# Esp32_USB.net
KiCad netlist of a schematic drawn in Altium Designer
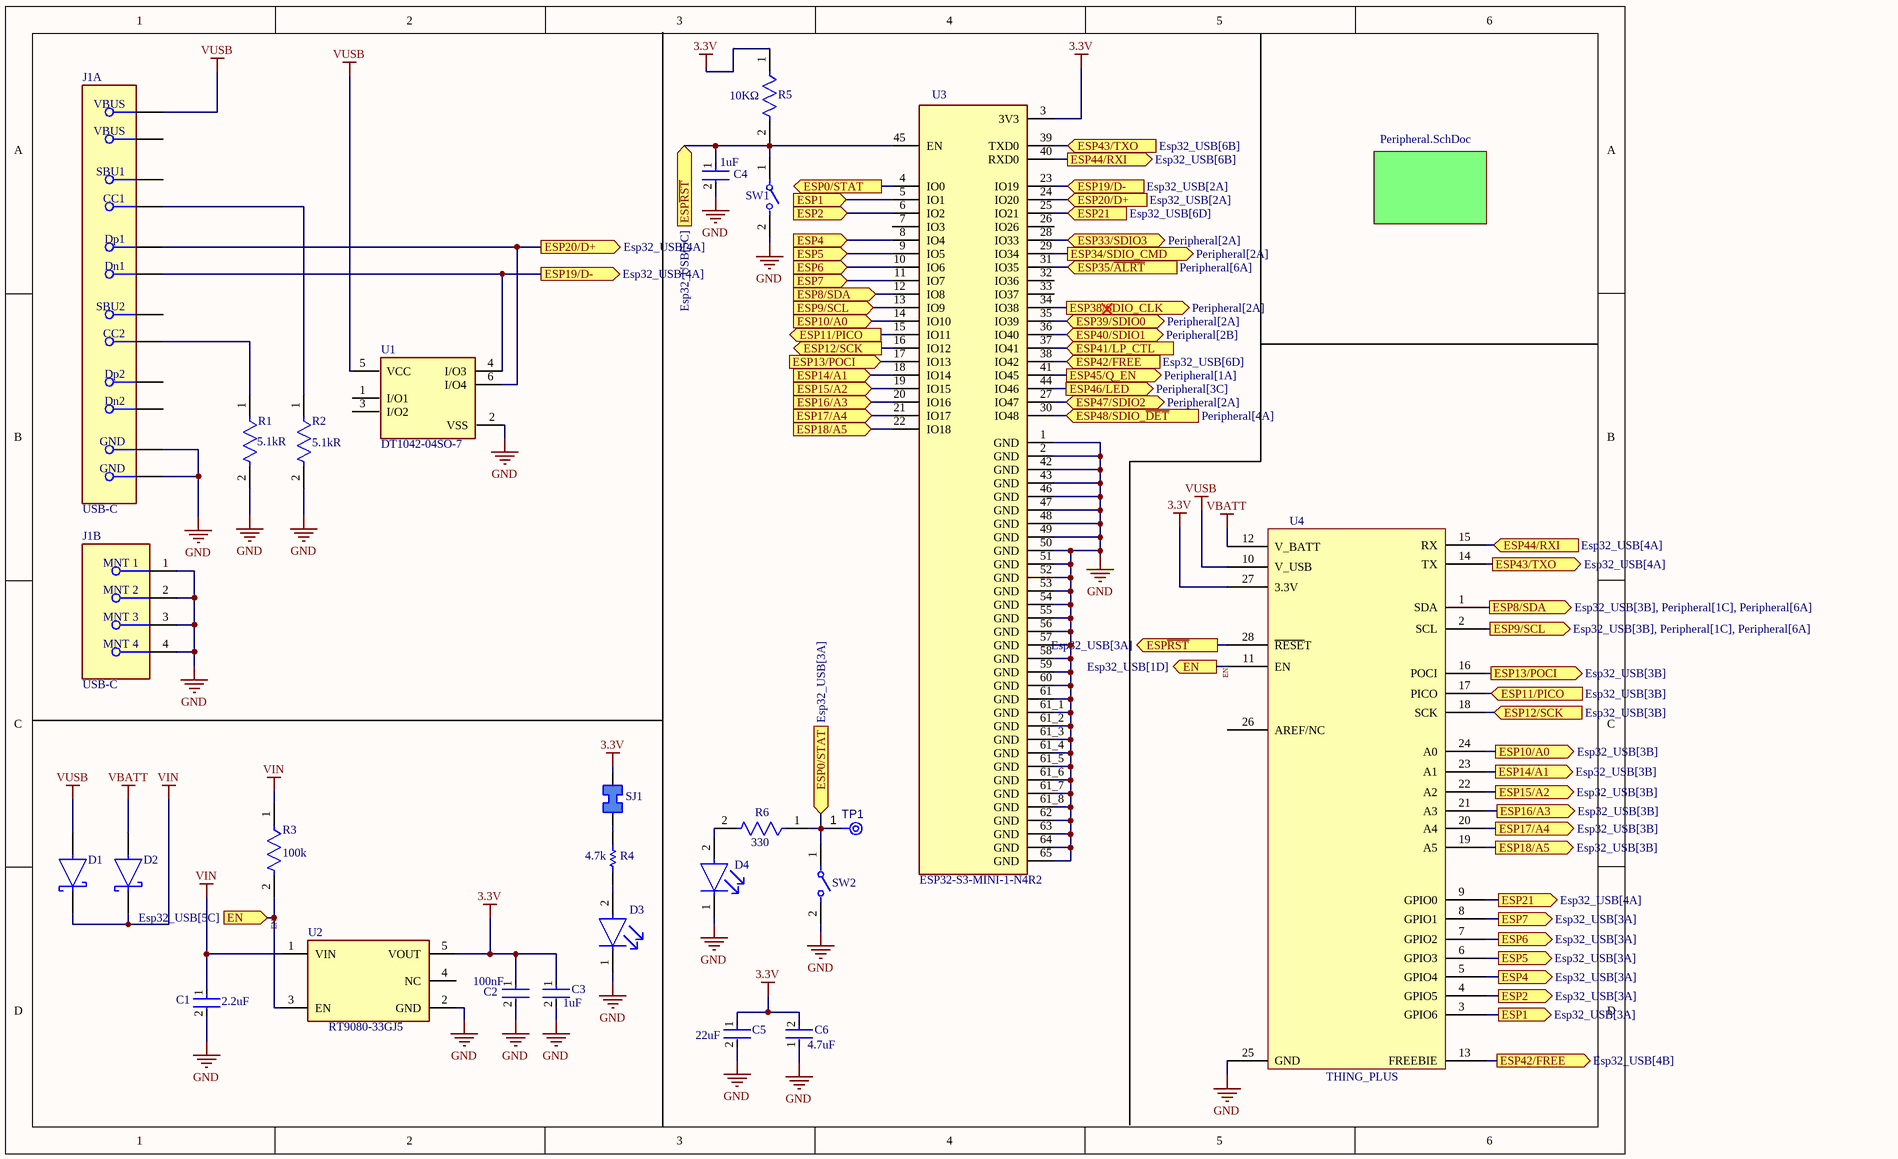
[diagram p0: Esp32_USB.SchDoc]

(export (version "E")
  (design (tool "Eeschema 10.0.6"))
  (components
    (comp (ref "C1")
      (value "GRM155C81A225KE44D")
      (footprint "FP-GRM155-0_1-IPC_C")
      (description "Chip Multilayer Ceramic Capacitors for General Purpose, 0402, 2.2uF, X6S, 22%, 10%, 10V")
      (fields (field (name "TOLERANCE") "10%") (field (name "CAPACITANCE") "2.2uF"))
      (libsource (lib "Altium Content Vault") (part "11868f565c42a9108669ba33697ecf6"))
    )
    (comp (ref "C2")
      (value "GRM033C70J104KE14D")
      (footprint "FP-GRM033-0_03-IPC_B")
      (description "Chip Multilayer Ceramic Capacitors for General Purpose, 0201, 0.10uF, X7S, 22%, 10%, 6.3V")
      (fields (field (name "CAPACITANCE") "100nF") (field (name "TOLERANCE") "10%"))
      (libsource (lib "Altium Content Vault") (part "b4654b650e69147ec39a6b967a45e02"))
    )
    (comp (ref "C3")
      (value "GRM155R61C105KA12D")
      (footprint "FP-GRM155-0_05-IPC_C")
      (description "Chip Multilayer Ceramic Capacitors for General Purpose, 0402, 1.0uF, X5R, 15%, 10%, 16V")
      (fields
        (field (name "CAPACITANCE") "1uF")
        (field (name "VOLTAGE") "16V")
        (field (name "TOLERANCE") "10%")
      )
      (libsource (lib "Altium Content Vault") (part "02cd4be3c70576c341d710602a673aa"))
    )
    (comp (ref "C4")
      (value "EMK105BJ105KVHF")
      (footprint "FP-0402-L_1_0_0_05-W_0_5-IPC_B")
      (description "None")
      (fields (field (name "CAPACITANCE") "1uF") (field (name "TOLERANCE") "10%"))
      (libsource (lib "Altium Content Vault") (part "b4654b650e69147ec39a6b967a45e02"))
    )
    (comp (ref "C5")
      (value "JMK107BC6226MA-T")
      (footprint "FP-0603-L_1_6_0_2-W_0_8_0-IPC_B")
      (description "Multilayer Ceramic Capacitor 22uF 6.3V X6S 20% SMD 0603 T/R")
      (fields (field (name "CAPACITANCE") "22uF") (field (name "TOLERANCE") "20%"))
      (libsource (lib "Altium Content Vault") (part "b4654b650e69147ec39a6b967a45e02"))
    )
    (comp (ref "C6")
      (value "JMK105BC6475MV-F")
      (footprint "FP-0402-L_1_0_0_15-W_0_5-IPC_C")
      (description "None")
      (fields (field (name "CAPACITANCE") "4.7uF") (field (name "TOLERANCE") "20%"))
      (libsource (lib "Altium Content Vault") (part "236180d848d6139a670b325ea6854c9"))
    )
    (comp (ref "D1")
      (value "BAT60AE6327HTSA1")
      (footprint "FP-PG-SOD323-2-IPC_C")
      (description "DIODE SCHOTTKY 10V 3A SOD323-2")
      (libsource (lib "Altium Content Vault") (part "1d6ec82d83fb6aee721767c19dac4b9"))
    )
    (comp (ref "D2")
      (value "BAT60AE6327HTSA1")
      (footprint "FP-PG-SOD323-2-IPC_C")
      (description "DIODE SCHOTTKY 10V 3A SOD323-2")
      (libsource (lib "Altium Content Vault") (part "1d6ec82d83fb6aee721767c19dac4b9"))
    )
    (comp (ref "D3")
      (value "LTST-C191KRKT")
      (footprint "FP-LTST-C191KRKT-MFG")
      (fields (field (name "VOLTAGE") "2V"))
      (libsource (lib "Altium Content Vault") (part "8706943c75ba83719d021d2fdc84c58"))
    )
    (comp (ref "D4")
      (value "LTST-C194TGKT")
      (footprint "FP-LTST-C194TGKT-MFG")
      (description "LED GREEN CLEAR SMD")
      (libsource (lib "Altium Content Vault") (part "8706943c75ba83719d021d2fdc84c58"))
    )
    (comp (ref "J1")
      (value "USB-C")
      (footprint "FP-2171790001-MFG")
      (description "CONN RCP USB2.0 TYP C 24P SMD RA")
      (libsource (lib "Altium Content Vault") (part "8b86497a633d14b3f74642136fc0ce6"))
    )
    (comp (ref "R1")
      (value "AC0402JR-075K1L")
      (footprint "FP-AC0402-IPC_C")
      (description "RES 5.1kΩ ±5% 0.063W 0402")
      (fields (field (name "TOLERANCE") "5%") (field (name "RESISTANCE") "5.1kR"))
      (libsource (lib "Altium Content Vault") (part "1029c3af85768c4190bb7ad29bc67b5"))
    )
    (comp (ref "R2")
      (value "AC0402JR-075K1L")
      (footprint "FP-AC0402-IPC_C")
      (description "RES 5.1kΩ ±5% 0.063W 0402")
      (fields (field (name "TOLERANCE") "5%") (field (name "RESISTANCE") "5.1kR"))
      (libsource (lib "Altium Content Vault") (part "1029c3af85768c4190bb7ad29bc67b5"))
    )
    (comp (ref "R3")
      (value "CRCW0402100KFKEDC")
      (footprint "FP-CRCW0402-C-e3-MFG")
      (description "RES 100K OHM 1% 1/16W 0402")
      (fields (field (name "TOLERANCE") "1%") (field (name "RESISTANCE") "100k"))
      (libsource (lib "Altium Content Vault") (part "1029c3af85768c4190bb7ad29bc67b5"))
    )
    (comp (ref "R4")
      (value "CRCW04024K70FKEDHP")
      (footprint "RESC1005X40X25LL05T10")
      (fields (field (name "MANUFACTURER") "Vishay Dale") (field (name "RESISTANCE") "4.7k"))
      (libsource (lib "Altium Content Vault") (part "RES"))
    )
    (comp (ref "R5")
      (value "10KΩ")
      (footprint "FP-RT0201-MFG")
      (description "RES SMD 10K OHM 1% 1/20W 0201")
      (fields
        (field (name "MANUFACTURER PART NUMBER") "RT0201FRE0710KL")
        (field (name "MANUFACTURER") "Yageo")
      )
      (libsource (lib "Altium Content Vault") (part "1029c3af85768c4190bb7ad29bc67b5"))
    )
    (comp (ref "R6")
      (value "AC0603FR-07330RL")
      (footprint "FP-AC0603-MFG")
      (description "RES 330Ω 1.00% 0.1W 0603")
      (fields (field (name "TOLERANCE") "1%") (field (name "RESISTANCE") "330"))
      (libsource (lib "Altium Content Vault") (part "1029c3af85768c4190bb7ad29bc67b5"))
    )
    (comp (ref "SJ1")
      (value "Solder Jumper")
      (footprint "Solder Jumper-Footprint-1")
      (description "2 pad Solder Jumper")
      (libsource (lib "Shuvendu Das") (part "Solder Jumper"))
    )
    (comp (ref "SW1")
      (value "FSM2JART")
      (footprint "FP-FSM2JART-MFG")
      (description "SWITCH TACTILE SPST-NO 0.05A 12V")
      (libsource (lib "Altium Content Vault") (part "bb27bde45df87f1f469753f287ef5ae"))
    )
    (comp (ref "SW2")
      (value "FSM2JART")
      (footprint "FP-FSM2JART-MFG")
      (description "SWITCH TACTILE SPST-NO 0.05A 12V")
      (libsource (lib "Altium Content Vault") (part "bb27bde45df87f1f469753f287ef5ae"))
    )
    (comp (ref "TP1")
      (value "TPAD6R")
      (footprint "TP06R")
      (description "0.6mm round")
      (libsource (lib "Shuvendu Das") (part "CMP-001-0001-4"))
    )
    (comp (ref "U1")
      (value "DT1042-04SO-7")
      (footprint "FP-SOT26_SC74R-MFG")
      (description "TVS DIODE 5V 9V SOT26")
      (fields
        (field (name "OCTOPART") "https://octopart.com/dt1042-04so-7-diodes+inc.-30954914")
        (field (name "MANUFACTURER") "Diodes Inc.")
      )
      (libsource (lib "Altium Content Vault") (part "2c77ea90e9f66181a10a8f2fa0beca8"))
    )
    (comp (ref "U2")
      (value "RT9080-33GJ5")
      (footprint "FP-RT9080-33GJ5-IPC_C")
      (description "IC REG LIN 3.3V 600MA TSOT23-5")
      (libsource (lib "Altium Content Vault") (part "f644620f29190e8f0733f9129712cb2"))
    )
    (comp (ref "U3")
      (value "ESP32-S3-MINI-1-N4R2")
      (footprint "XCVR_ESP32-S3-MINI-1-N4R2")
      (description "Bluetooth, WiFi 802.11b/g/n, Bluetooth v5.0 Transceiver Module 2.4GHz PCB Trace Surface Mount")
      (fields (field (name "MF") "Espressif Systems"))
      (libsource (lib "ESP32-S3-MINI-1-N4R2") (part "ESP32-S3-MINI-1-N4R2"))
    )
    (comp (ref "U4") (value "THING_PLUS") (libsource (lib "Thing_plus") (part "THING_PLUS")))
  )
  (nets
    (net (code "1") (name "/EN") (class "Default")
      (node (ref "R3") (pin "2") (pinfunction "2_2") (pintype "passive"))
      (node (ref "U2") (pin "3") (pinfunction "EN_3") (pintype "passive"))
      (node (ref "U4") (pin "11") (pinfunction "EN_11") (pintype "passive"))
    )
    (net (code "2") (name "/ESP0{slash}STAT") (class "Default")
      (node (ref "R6") (pin "1") (pinfunction "1_1") (pintype "passive"))
      (node (ref "SW2") (pin "1") (pinfunction "1_1") (pintype "passive"))
      (node (ref "TP1") (pin "1") (pinfunction "TP_1") (pintype "passive"))
      (node (ref "U3") (pin "4") (pinfunction "IO0_4") (pintype "passive"))
    )
    (net (code "3") (name "/ESP1") (class "Default")
      (node (ref "U3") (pin "5") (pinfunction "IO1_5") (pintype "passive"))
      (node (ref "U4") (pin "3") (pinfunction "GPIO6_3") (pintype "passive"))
    )
    (net (code "4") (name "/ESP2") (class "Default")
      (node (ref "U3") (pin "6") (pinfunction "IO2_6") (pintype "passive"))
      (node (ref "U4") (pin "4") (pinfunction "GPIO5_4") (pintype "passive"))
    )
    (net (code "5") (name "/ESP4") (class "Default")
      (node (ref "U3") (pin "8") (pinfunction "IO4_8") (pintype "passive"))
      (node (ref "U4") (pin "5") (pinfunction "GPIO4_5") (pintype "passive"))
    )
    (net (code "6") (name "/ESP5") (class "Default")
      (node (ref "U3") (pin "9") (pinfunction "IO5_9") (pintype "passive"))
      (node (ref "U4") (pin "6") (pinfunction "GPIO3_6") (pintype "passive"))
    )
    (net (code "7") (name "/ESP6") (class "Default")
      (node (ref "U3") (pin "10") (pinfunction "IO6_10") (pintype "passive"))
      (node (ref "U4") (pin "7") (pinfunction "GPIO2_7") (pintype "passive"))
    )
    (net (code "8") (name "/ESP7") (class "Default")
      (node (ref "U3") (pin "11") (pinfunction "IO7_11") (pintype "passive"))
      (node (ref "U4") (pin "8") (pinfunction "GPIO1_8") (pintype "passive"))
    )
    (net (code "9") (name "/ESP8{slash}SDA") (class "Default")
      (node (ref "U3") (pin "12") (pinfunction "IO8_12") (pintype "passive"))
      (node (ref "U4") (pin "1") (pinfunction "SDA_1") (pintype "passive"))
    )
    (net (code "10") (name "/ESP9{slash}SCL") (class "Default")
      (node (ref "U3") (pin "13") (pinfunction "IO9_13") (pintype "passive"))
      (node (ref "U4") (pin "2") (pinfunction "SCL_2") (pintype "passive"))
    )
    (net (code "11") (name "/ESP10{slash}A0") (class "Default")
      (node (ref "U3") (pin "14") (pinfunction "IO10_14") (pintype "passive"))
      (node (ref "U4") (pin "24") (pinfunction "A0_24") (pintype "passive"))
    )
    (net (code "12") (name "/ESP11{slash}PICO") (class "Default")
      (node (ref "U3") (pin "15") (pinfunction "IO11_15") (pintype "passive"))
      (node (ref "U4") (pin "17") (pinfunction "PICO_17") (pintype "passive"))
    )
    (net (code "13") (name "/ESP12{slash}SCK") (class "Default")
      (node (ref "U3") (pin "16") (pinfunction "IO12_16") (pintype "passive"))
      (node (ref "U4") (pin "18") (pinfunction "SCK_18") (pintype "passive"))
    )
    (net (code "14") (name "/ESP13{slash}POCI") (class "Default")
      (node (ref "U3") (pin "17") (pinfunction "IO13_17") (pintype "passive"))
      (node (ref "U4") (pin "16") (pinfunction "POCI_16") (pintype "passive"))
    )
    (net (code "15") (name "/ESP14{slash}A1") (class "Default")
      (node (ref "U3") (pin "18") (pinfunction "IO14_18") (pintype "passive"))
      (node (ref "U4") (pin "23") (pinfunction "A1_23") (pintype "passive"))
    )
    (net (code "16") (name "/ESP15{slash}A2") (class "Default")
      (node (ref "U3") (pin "19") (pinfunction "IO15_19") (pintype "passive"))
      (node (ref "U4") (pin "22") (pinfunction "A2_22") (pintype "passive"))
    )
    (net (code "17") (name "/ESP16{slash}A3") (class "Default")
      (node (ref "U3") (pin "20") (pinfunction "IO16_20") (pintype "passive"))
      (node (ref "U4") (pin "21") (pinfunction "A3_21") (pintype "passive"))
    )
    (net (code "18") (name "/ESP17{slash}A4") (class "Default")
      (node (ref "U3") (pin "21") (pinfunction "IO17_21") (pintype "passive"))
      (node (ref "U4") (pin "20") (pinfunction "A4_20") (pintype "passive"))
    )
    (net (code "19") (name "/ESP18{slash}A5") (class "Default")
      (node (ref "U3") (pin "22") (pinfunction "IO18_22") (pintype "passive"))
      (node (ref "U4") (pin "19") (pinfunction "A5_19") (pintype "passive"))
    )
    (net (code "20") (name "/ESP19{slash}D-") (class "Default")
      (node (ref "J1") (pin "A7") (pinfunction "Dn1_A7") (pintype "passive"))
      (node (ref "U1") (pin "4") (pinfunction "I/O3_4") (pintype "passive"))
      (node (ref "U3") (pin "23") (pinfunction "IO19_23") (pintype "passive"))
    )
    (net (code "21") (name "/ESP20{slash}D+") (class "Default")
      (node (ref "J1") (pin "A6") (pinfunction "Dp1_A6") (pintype "passive"))
      (node (ref "U1") (pin "6") (pinfunction "I/O4_6") (pintype "passive"))
      (node (ref "U3") (pin "24") (pinfunction "IO20_24") (pintype "passive"))
    )
    (net (code "22") (name "/ESP21") (class "Default")
      (node (ref "U3") (pin "25") (pinfunction "IO21_25") (pintype "passive"))
      (node (ref "U4") (pin "9") (pinfunction "GPIO0_9") (pintype "passive"))
    )
    (net (code "23") (name "/ESP33{slash}SDIO3") (class "Default")
      (node (ref "U3") (pin "28") (pinfunction "IO33_28") (pintype "passive"))
    )
    (net (code "24") (name "/ESP34{slash}SDIO_CMD") (class "Default")
      (node (ref "U3") (pin "29") (pinfunction "IO34_29") (pintype "passive"))
    )
    (net (code "25") (name "/ESP35{slash}~{ALRT}") (class "Default")
      (node (ref "U3") (pin "31") (pinfunction "IO35_31") (pintype "passive"))
    )
    (net (code "26") (name "/ESP38{slash}SDIO_CLK") (class "Default")
      (node (ref "U3") (pin "34") (pinfunction "IO38_34") (pintype "passive"))
    )
    (net (code "27") (name "/ESP39{slash}SDIO0") (class "Default")
      (node (ref "U3") (pin "35") (pinfunction "IO39_35") (pintype "passive"))
    )
    (net (code "28") (name "/ESP40{slash}SDIO1") (class "Default")
      (node (ref "U3") (pin "36") (pinfunction "IO40_36") (pintype "passive"))
    )
    (net (code "29") (name "/ESP41{slash}LP_CTL") (class "Default")
      (node (ref "U3") (pin "37") (pinfunction "IO41_37") (pintype "passive"))
    )
    (net (code "30") (name "/ESP42{slash}FREE") (class "Default")
      (node (ref "U3") (pin "38") (pinfunction "IO42_38") (pintype "passive"))
      (node (ref "U4") (pin "13") (pinfunction "FREEBIE_13") (pintype "passive"))
    )
    (net (code "31") (name "/ESP43{slash}TXO") (class "Default")
      (node (ref "U3") (pin "39") (pinfunction "TXD0_39") (pintype "passive"))
      (node (ref "U4") (pin "14") (pinfunction "TX_14") (pintype "passive"))
    )
    (net (code "32") (name "/ESP44{slash}RXI") (class "Default")
      (node (ref "U3") (pin "40") (pinfunction "RXD0_40") (pintype "passive"))
      (node (ref "U4") (pin "15") (pinfunction "RX_15") (pintype "passive"))
    )
    (net (code "33") (name "/ESP45{slash}Q_EN") (class "Default")
      (node (ref "U3") (pin "41") (pinfunction "IO45_41") (pintype "passive"))
    )
    (net (code "34") (name "/ESP46{slash}LED") (class "Default")
      (node (ref "U3") (pin "44") (pinfunction "IO46_44") (pintype "passive"))
    )
    (net (code "35") (name "/ESP47{slash}SDIO2") (class "Default")
      (node (ref "U3") (pin "27") (pinfunction "IO47_27") (pintype "passive"))
    )
    (net (code "36") (name "/ESP48{slash}SDIO_~{DET}") (class "Default")
      (node (ref "U3") (pin "30") (pinfunction "IO48_30") (pintype "passive"))
    )
    (net (code "37") (name "/ESP~{RST}") (class "Default")
      (node (ref "C4") (pin "1") (pinfunction "1_1") (pintype "passive"))
      (node (ref "R5") (pin "2") (pinfunction "2_2") (pintype "passive"))
      (node (ref "SW1") (pin "1") (pinfunction "1_1") (pintype "passive"))
      (node (ref "U3") (pin "45") (pinfunction "EN_45") (pintype "passive"))
      (node (ref "U4") (pin "28") (pinfunction "~{RESE}T_28") (pintype "passive"))
    )
    (net (code "38") (name "3.3V") (class "Default")
      (node (ref "C2") (pin "1") (pinfunction "1_1") (pintype "passive"))
      (node (ref "C3") (pin "1") (pinfunction "1_1") (pintype "passive"))
      (node (ref "C5") (pin "1") (pinfunction "1_1") (pintype "passive"))
      (node (ref "C6") (pin "2") (pinfunction "2_2") (pintype "passive"))
      (node (ref "R5") (pin "1") (pinfunction "1_1") (pintype "passive"))
      (node (ref "SJ1") (pin "1") (pinfunction "1_1") (pintype "passive"))
      (node (ref "U2") (pin "5") (pinfunction "VOUT_5") (pintype "passive"))
      (node (ref "U3") (pin "3") (pinfunction "3V3_3") (pintype "power_in"))
      (node (ref "U4") (pin "27") (pinfunction "3.3V_27") (pintype "passive"))
    )
    (net (code "39") (name "GND") (class "Default")
      (node (ref "C1") (pin "2") (pinfunction "2_2") (pintype "passive"))
      (node (ref "C2") (pin "2") (pinfunction "2_2") (pintype "passive"))
      (node (ref "C3") (pin "2") (pinfunction "2_2") (pintype "passive"))
      (node (ref "C4") (pin "2") (pinfunction "2_2") (pintype "passive"))
      (node (ref "C5") (pin "2") (pinfunction "2_2") (pintype "passive"))
      (node (ref "C6") (pin "1") (pinfunction "1_1") (pintype "passive"))
      (node (ref "D3") (pin "1") (pinfunction "C_1") (pintype "passive"))
      (node (ref "D4") (pin "1") (pinfunction "C_1") (pintype "passive"))
      (node (ref "J1") (pin "1") (pinfunction "MNT_1_1") (pintype "passive"))
      (node (ref "J1") (pin "2") (pinfunction "MNT_2_2") (pintype "passive"))
      (node (ref "J1") (pin "3") (pinfunction "MNT_3_3") (pintype "power_in"))
      (node (ref "J1") (pin "4") (pinfunction "MNT_4_4") (pintype "power_in"))
      (node (ref "J1") (pin "A1-B12") (pinfunction "GND_A1-B12") (pintype "power_in"))
      (node (ref "J1") (pin "B1-A12") (pinfunction "GND_B1-A12") (pintype "power_in"))
      (node (ref "R1") (pin "2") (pinfunction "2_2") (pintype "passive"))
      (node (ref "R2") (pin "2") (pinfunction "2_2") (pintype "passive"))
      (node (ref "SW1") (pin "2") (pinfunction "2_2") (pintype "passive"))
      (node (ref "SW2") (pin "2") (pinfunction "2_2") (pintype "passive"))
      (node (ref "U1") (pin "2") (pinfunction "VSS_2") (pintype "power_in"))
      (node (ref "U2") (pin "2") (pinfunction "GND_2") (pintype "power_in"))
      (node (ref "U3") (pin "1") (pinfunction "GND_1") (pintype "power_in"))
      (node (ref "U3") (pin "2") (pinfunction "GND_2") (pintype "power_in"))
      (node (ref "U3") (pin "42") (pinfunction "GND_42") (pintype "power_in"))
      (node (ref "U3") (pin "43") (pinfunction "GND_43") (pintype "power_in"))
      (node (ref "U3") (pin "46") (pinfunction "GND_46") (pintype "power_in"))
      (node (ref "U3") (pin "47") (pinfunction "GND_47") (pintype "power_in"))
      (node (ref "U3") (pin "48") (pinfunction "GND_48") (pintype "power_in"))
      (node (ref "U3") (pin "49") (pinfunction "GND_49") (pintype "power_in"))
      (node (ref "U3") (pin "50") (pinfunction "GND_50") (pintype "power_in"))
      (node (ref "U3") (pin "51") (pinfunction "GND_51") (pintype "power_in"))
      (node (ref "U3") (pin "52") (pinfunction "GND_52") (pintype "power_in"))
      (node (ref "U3") (pin "53") (pinfunction "GND_53") (pintype "power_in"))
      (node (ref "U3") (pin "54") (pinfunction "GND_54") (pintype "power_in"))
      (node (ref "U3") (pin "55") (pinfunction "GND_55") (pintype "power_in"))
      (node (ref "U3") (pin "56") (pinfunction "GND_56") (pintype "power_in"))
      (node (ref "U3") (pin "57") (pinfunction "GND_57") (pintype "power_in"))
      (node (ref "U3") (pin "58") (pinfunction "GND_58") (pintype "power_in"))
      (node (ref "U3") (pin "59") (pinfunction "GND_59") (pintype "power_in"))
      (node (ref "U3") (pin "60") (pinfunction "GND_60") (pintype "power_in"))
      (node (ref "U3") (pin "61") (pinfunction "GND_61") (pintype "power_in"))
      (node (ref "U3") (pin "61_1") (pinfunction "GND_61_1") (pintype "power_in"))
      (node (ref "U3") (pin "61_2") (pinfunction "GND_61_2") (pintype "power_in"))
      (node (ref "U3") (pin "61_3") (pinfunction "GND_61_3") (pintype "power_in"))
      (node (ref "U3") (pin "61_4") (pinfunction "GND_61_4") (pintype "power_in"))
      (node (ref "U3") (pin "61_5") (pinfunction "GND_61_5") (pintype "power_in"))
      (node (ref "U3") (pin "61_6") (pinfunction "GND_61_6") (pintype "power_in"))
      (node (ref "U3") (pin "61_7") (pinfunction "GND_61_7") (pintype "power_in"))
      (node (ref "U3") (pin "61_8") (pinfunction "GND_61_8") (pintype "power_in"))
      (node (ref "U3") (pin "62") (pinfunction "GND_62") (pintype "power_in"))
      (node (ref "U3") (pin "63") (pinfunction "GND_63") (pintype "power_in"))
      (node (ref "U3") (pin "64") (pinfunction "GND_64") (pintype "power_in"))
      (node (ref "U3") (pin "65") (pinfunction "GND_65") (pintype "power_in"))
      (node (ref "U4") (pin "25") (pinfunction "GND_25") (pintype "passive"))
    )
    (net (code "40") (name "Net-(D3-A)") (class "Default")
      (node (ref "D3") (pin "2") (pinfunction "A_2") (pintype "passive"))
      (node (ref "R4") (pin "2") (pinfunction "2_2") (pintype "passive"))
    )
    (net (code "41") (name "Net-(D4-A)") (class "Default")
      (node (ref "D4") (pin "2") (pinfunction "A_2") (pintype "passive"))
      (node (ref "R6") (pin "2") (pinfunction "2_2") (pintype "passive"))
    )
    (net (code "42") (name "Net-(J1A-CC1)") (class "Default")
      (node (ref "J1") (pin "A5") (pinfunction "CC1_A5") (pintype "passive"))
      (node (ref "R2") (pin "1") (pinfunction "1_1") (pintype "passive"))
    )
    (net (code "43") (name "Net-(J1A-CC2)") (class "Default")
      (node (ref "J1") (pin "B5") (pinfunction "CC2_B5") (pintype "passive"))
      (node (ref "R1") (pin "1") (pinfunction "1_1") (pintype "passive"))
    )
    (net (code "44") (name "Net-(R4-Pad1)") (class "Default")
      (node (ref "R4") (pin "1") (pinfunction "1_1") (pintype "passive"))
      (node (ref "SJ1") (pin "2") (pinfunction "2_2") (pintype "passive"))
    )
    (net (code "45") (name "VBATT") (class "Default")
      (node (ref "D2") (pin "2") (pinfunction "A_2") (pintype "passive"))
      (node (ref "U4") (pin "12") (pinfunction "V_BATT_12") (pintype "passive"))
    )
    (net (code "46") (name "VIN") (class "Default")
      (node (ref "C1") (pin "1") (pinfunction "1_1") (pintype "passive"))
      (node (ref "D1") (pin "1") (pinfunction "C_1") (pintype "passive"))
      (node (ref "D2") (pin "1") (pinfunction "C_1") (pintype "passive"))
      (node (ref "R3") (pin "1") (pinfunction "1_1") (pintype "passive"))
      (node (ref "U2") (pin "1") (pinfunction "VIN_1") (pintype "power_in"))
    )
    (net (code "47") (name "VUSB") (class "Default")
      (node (ref "D1") (pin "2") (pinfunction "A_2") (pintype "passive"))
      (node (ref "J1") (pin "A4-B9") (pinfunction "VBUS_A4-B9") (pintype "power_in"))
      (node (ref "U1") (pin "5") (pinfunction "VCC_5") (pintype "power_in"))
      (node (ref "U4") (pin "10") (pinfunction "V_USB_10") (pintype "passive"))
    )
    (net (code "48") (name "unconnected-(J1A-Dn2-PadB7)") (class "Default")
      (node (ref "J1") (pin "B7") (pinfunction "Dn2_B7") (pintype "passive"))
    )
    (net (code "49") (name "unconnected-(J1A-Dp2-PadB6)") (class "Default")
      (node (ref "J1") (pin "B6") (pinfunction "Dp2_B6") (pintype "passive"))
    )
    (net (code "50") (name "unconnected-(J1A-SBU1-PadA8)") (class "Default")
      (node (ref "J1") (pin "A8") (pinfunction "SBU1_A8") (pintype "passive"))
    )
    (net (code "51") (name "unconnected-(J1A-SBU2-PadB8)") (class "Default")
      (node (ref "J1") (pin "B8") (pinfunction "SBU2_B8") (pintype "passive"))
    )
    (net (code "52") (name "unconnected-(J1A-VBUS-PadB4-A9)") (class "Default")
      (node (ref "J1") (pin "B4-A9") (pinfunction "VBUS_B4-A9") (pintype "power_in"))
    )
    (net (code "53") (name "unconnected-(U1-I{slash}O1-Pad1)") (class "Default")
      (node (ref "U1") (pin "1") (pinfunction "I/O1_1") (pintype "passive"))
    )
    (net (code "54") (name "unconnected-(U1-I{slash}O2-Pad3)") (class "Default")
      (node (ref "U1") (pin "3") (pinfunction "I/O2_3") (pintype "passive"))
    )
    (net (code "55") (name "unconnected-(U2-NC-Pad4)") (class "Default")
      (node (ref "U2") (pin "4") (pinfunction "NC_4") (pintype "passive"))
    )
    (net (code "56") (name "unconnected-(U3-IO3-Pad7)") (class "Default")
      (node (ref "U3") (pin "7") (pinfunction "IO3_7") (pintype "passive"))
    )
    (net (code "57") (name "unconnected-(U3-IO26-Pad26)") (class "Default")
      (node (ref "U3") (pin "26") (pinfunction "IO26_26") (pintype "passive"))
    )
    (net (code "58") (name "unconnected-(U3-IO36-Pad32)") (class "Default")
      (node (ref "U3") (pin "32") (pinfunction "IO36_32") (pintype "passive"))
    )
    (net (code "59") (name "unconnected-(U3-IO37-Pad33)") (class "Default")
      (node (ref "U3") (pin "33") (pinfunction "IO37_33") (pintype "passive"))
    )
    (net (code "60") (name "unconnected-(U4-AREF{slash}NC-Pad26)") (class "Default")
      (node (ref "U4") (pin "26") (pinfunction "AREF/NC_26") (pintype "passive"))
    )
  )
)
